# CAN.net
KiCad netlist of a schematic drawn in Altium Designer
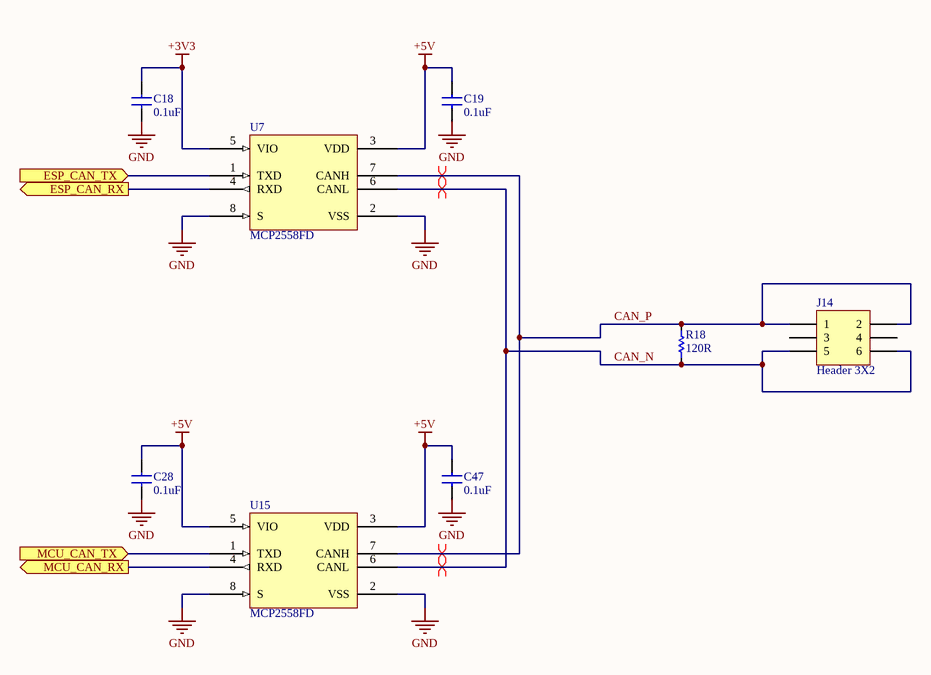
[diagram p0: CAN.SchDoc]

(export (version "E")
  (design (tool "Eeschema 10.0.6"))
  (components
    (comp (ref "C18")
      (value "0.1uF")
      (footprint "0402_CAPACITOR")
      (description "CAP CERM 0.1uF 10% 16V 0402")
      (fields (field (name "VOLTAGE") "16V") (field (name "Comment") "CAP 0.1uF 16V X7R"))
      (libsource (lib "capacitor") (part "C_0402_0.1uF_16V_10%"))
    )
    (comp (ref "C19")
      (value "0.1uF")
      (footprint "0402_CAPACITOR")
      (description "CAP CERM 0.1uF 10% 16V 0402")
      (fields (field (name "VOLTAGE") "16V") (field (name "Comment") "CAP 0.1uF 16V X7R"))
      (libsource (lib "capacitor") (part "C_0402_0.1uF_16V_10%"))
    )
    (comp (ref "C28")
      (value "0.1uF")
      (footprint "0402_CAPACITOR")
      (description "CAP CERM 0.1uF 10% 16V 0402")
      (fields (field (name "VOLTAGE") "16V") (field (name "Comment") "CAP 0.1uF 16V X7R"))
      (libsource (lib "capacitor") (part "C_0402_0.1uF_16V_10%"))
    )
    (comp (ref "C47")
      (value "0.1uF")
      (footprint "0402_CAPACITOR")
      (description "CAP CERM 0.1uF 10% 16V 0402")
      (fields (field (name "VOLTAGE") "16V") (field (name "Comment") "CAP 0.1uF 16V X7R"))
      (libsource (lib "capacitor") (part "C_0402_0.1uF_16V_10%"))
    )
    (comp (ref "J14")
      (value "Header 3X2")
      (footprint "HDR2X3")
      (description "Header, 3-Pin, Dual row")
      (fields (field (name "PUBLISHER") "Altium Limited"))
      (libsource (lib "Miscellaneous Connectors") (part "Header 3X2"))
    )
    (comp (ref "R18")
      (value "120R")
      (footprint "0805_Resistor")
      (description "Generic 0805 resistor (10.2R to 10M)")
      (fields (field (name "TOLERANCE") "±1%") (field (name "MANUFACTURER") "Yageo"))
      (libsource (lib "resistor") (part "R_0805_generic_1%"))
    )
    (comp (ref "U7")
      (value "MCP2558FD")
      (footprint "SOIC-8")
      (description "1/1 Transceiver CANbus 8-SOIC")
      (fields
        (field (name "MANUFACTURER") "Microchip")
        (field (name "MANUFACTURER PART NUMBER") "MCP2558FD-H/SN")
      )
      (libsource (lib "ic") (part "U_MCP2558FD"))
    )
    (comp (ref "U15")
      (value "MCP2558FD")
      (footprint "SOIC-8")
      (description "1/1 Transceiver CANbus 8-SOIC")
      (fields
        (field (name "MANUFACTURER") "Microchip")
        (field (name "MANUFACTURER PART NUMBER") "MCP2558FD-H/SN")
      )
      (libsource (lib "ic") (part "U_MCP2558FD"))
    )
  )
  (nets
    (net (code "1") (name "+3V3") (class "Default")
      (node (ref "C18") (pin "2") (pinfunction "2_2") (pintype "passive"))
      (node (ref "U7") (pin "5") (pinfunction "VIO_5") (pintype "input"))
    )
    (net (code "2") (name "+5V") (class "Default")
      (node (ref "C19") (pin "2") (pinfunction "2_2") (pintype "passive"))
      (node (ref "C28") (pin "2") (pinfunction "2_2") (pintype "passive"))
      (node (ref "C47") (pin "2") (pinfunction "2_2") (pintype "passive"))
      (node (ref "U15") (pin "3") (pinfunction "VDD_3") (pintype "power_in"))
      (node (ref "U15") (pin "5") (pinfunction "VIO_5") (pintype "input"))
      (node (ref "U7") (pin "3") (pinfunction "VDD_3") (pintype "power_in"))
    )
    (net (code "3") (name "/CAN_N") (class "Default")
      (node (ref "J14") (pin "5") (pinfunction "5_5") (pintype "passive"))
      (node (ref "J14") (pin "6") (pinfunction "6_6") (pintype "passive"))
      (node (ref "R18") (pin "1") (pinfunction "1_1") (pintype "passive"))
      (node (ref "U15") (pin "6") (pinfunction "CANL_6") (pintype "open_collector"))
      (node (ref "U7") (pin "6") (pinfunction "CANL_6") (pintype "open_collector"))
    )
    (net (code "4") (name "/CAN_P") (class "Default")
      (node (ref "J14") (pin "1") (pinfunction "1_1") (pintype "passive"))
      (node (ref "J14") (pin "2") (pinfunction "2_2") (pintype "passive"))
      (node (ref "R18") (pin "2") (pinfunction "2_2") (pintype "passive"))
      (node (ref "U15") (pin "7") (pinfunction "CANH_7") (pintype "open_emitter"))
      (node (ref "U7") (pin "7") (pinfunction "CANH_7") (pintype "open_emitter"))
    )
    (net (code "5") (name "/ESP_CAN_RX") (class "Default")
      (node (ref "U7") (pin "4") (pinfunction "RXD_4") (pintype "output"))
    )
    (net (code "6") (name "/ESP_CAN_TX") (class "Default")
      (node (ref "U7") (pin "1") (pinfunction "TXD_1") (pintype "input"))
    )
    (net (code "7") (name "/MCU_CAN_RX") (class "Default")
      (node (ref "U15") (pin "4") (pinfunction "RXD_4") (pintype "output"))
    )
    (net (code "8") (name "/MCU_CAN_TX") (class "Default")
      (node (ref "U15") (pin "1") (pinfunction "TXD_1") (pintype "input"))
    )
    (net (code "9") (name "GND") (class "Default")
      (node (ref "C18") (pin "1") (pinfunction "1_1") (pintype "passive"))
      (node (ref "C19") (pin "1") (pinfunction "1_1") (pintype "passive"))
      (node (ref "C28") (pin "1") (pinfunction "1_1") (pintype "passive"))
      (node (ref "C47") (pin "1") (pinfunction "1_1") (pintype "passive"))
      (node (ref "U15") (pin "2") (pinfunction "VSS_2") (pintype "power_in"))
      (node (ref "U15") (pin "8") (pinfunction "S_8") (pintype "input"))
      (node (ref "U7") (pin "2") (pinfunction "VSS_2") (pintype "power_in"))
      (node (ref "U7") (pin "8") (pinfunction "S_8") (pintype "input"))
    )
    (net (code "10") (name "unconnected-(J14-Pad3)") (class "Default")
      (node (ref "J14") (pin "3") (pinfunction "3_3") (pintype "passive"))
    )
    (net (code "11") (name "unconnected-(J14-Pad4)") (class "Default")
      (node (ref "J14") (pin "4") (pinfunction "4_4") (pintype "passive"))
    )
  )
)
